# connectors.net
KiCad netlist of a schematic drawn in Altium Designer
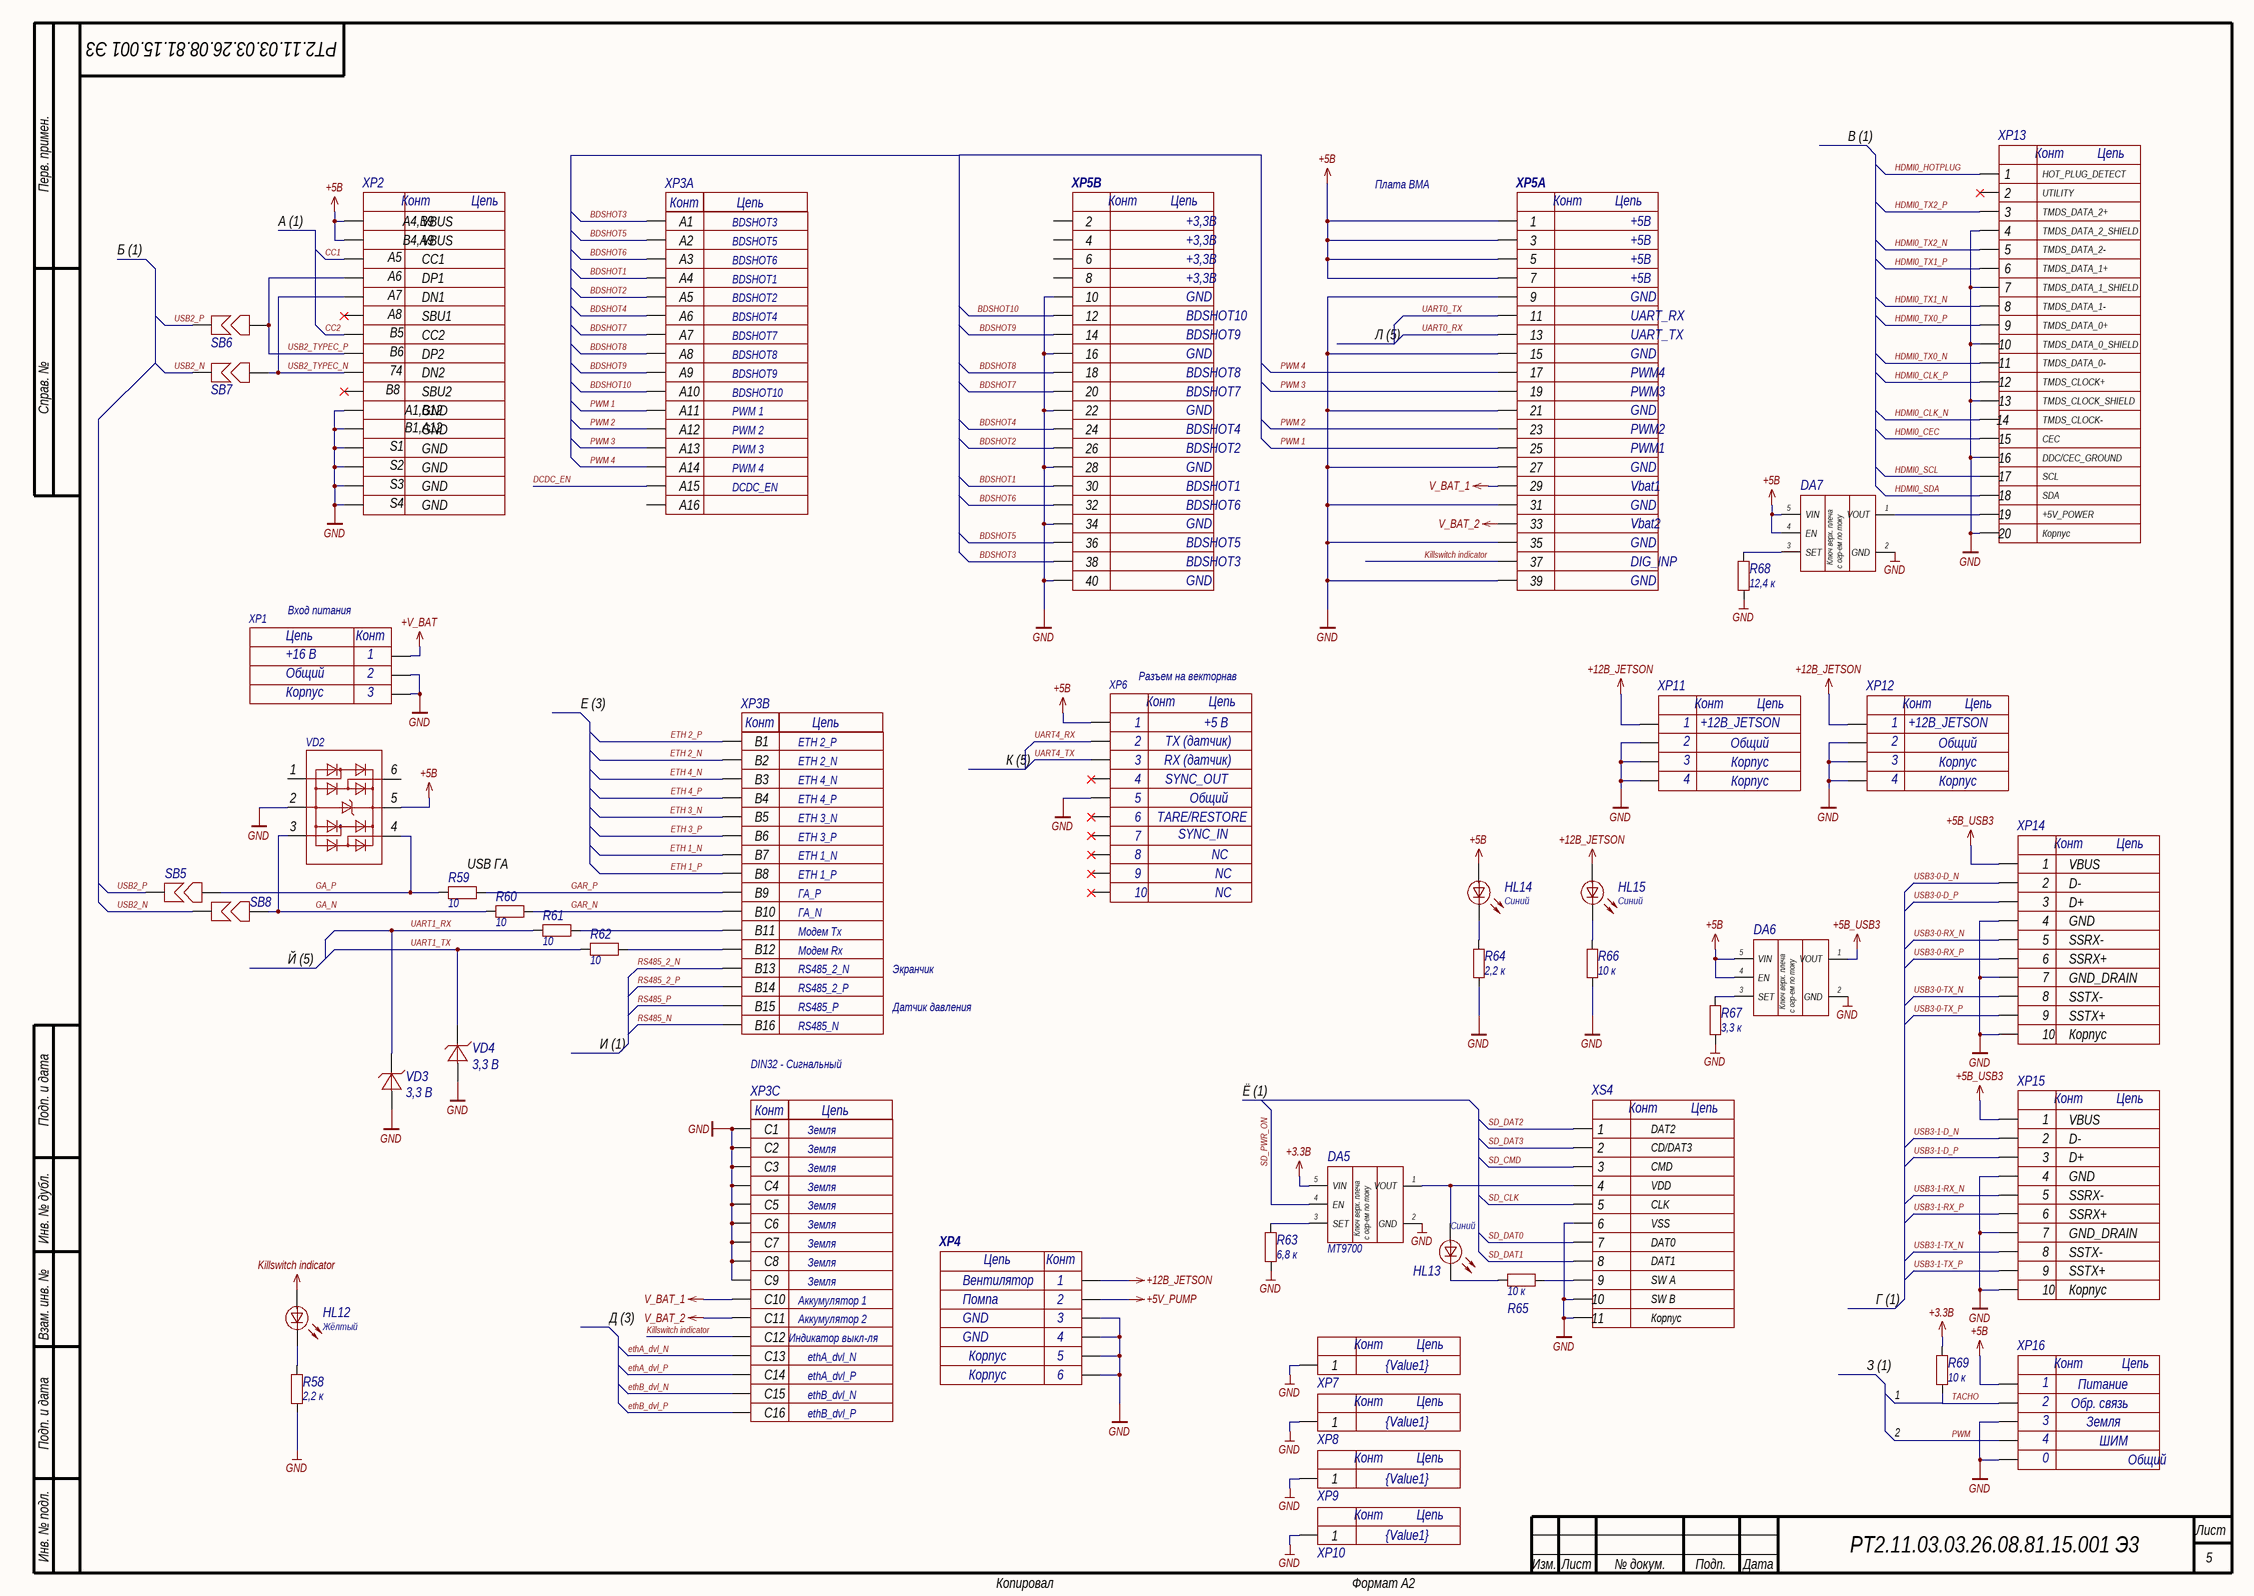
[diagram p0: connectors.SchDoc]

(export (version "E")
  (design (tool "Eeschema 10.0.6"))
  (components
    (comp (ref "DA5")
      (value "MT9700")
      (footprint "SOT23-5")
      (description "Силовой ключ с настраиваемым ограничением тока, 2А(max), SOT-23-5")
      (fields (field (name "АВТОР") "rreali"))
      (libsource (lib "Hydrolib") (part "MT9700"))
    )
    (comp (ref "DA6")
      (value "MT9700")
      (footprint "SOT23-5")
      (description "Силовой ключ с настраиваемым ограничением тока, 2А(max), SOT-23-5")
      (fields (field (name "АВТОР") "rreali"))
      (libsource (lib "Hydrolib") (part "MT9700"))
    )
    (comp (ref "DA7")
      (value "MT9700")
      (footprint "SOT23-5")
      (description "Силовой ключ с настраиваемым ограничением тока, 2А(max), SOT-23-5")
      (fields (field (name "АВТОР") "rreali"))
      (libsource (lib "Hydrolib") (part "MT9700"))
    )
    (comp (ref "HL12")
      (value "Жёлтый")
      (footprint "0603D_yellow")
      (description "Светодиод 0603 Жёлтый")
      (fields (field (name "PART NUMBER") "LED 0603 YELLOW") (field (name "АВТОР") "rreali"))
      (libsource (lib "Hydrolib") (part "LED"))
    )
    (comp (ref "HL13")
      (value "Синий")
      (footprint "0603D_blue")
      (description "Светодиод 0603 Синий")
      (fields (field (name "PART NUMBER") "LED 0603 BLUE") (field (name "АВТОР") "rreali"))
      (libsource (lib "Hydrolib") (part "LED"))
    )
    (comp (ref "HL14")
      (value "Синий")
      (footprint "0603D_blue")
      (description "Светодиод 0603 Синий")
      (fields (field (name "PART NUMBER") "LED 0603 BLUE") (field (name "АВТОР") "rreali"))
      (libsource (lib "Hydrolib") (part "LED"))
    )
    (comp (ref "HL15")
      (value "Синий")
      (footprint "0603D_blue")
      (description "Светодиод 0603 Синий")
      (fields (field (name "PART NUMBER") "LED 0603 BLUE") (field (name "АВТОР") "rreali"))
      (libsource (lib "Hydrolib") (part "LED"))
    )
    (comp (ref "R58")
      (value "2,2 к")
      (footprint "0603R")
      (description "Резистор номиналом 2,2 кОм 1%")
      (fields (field (name "PART NUMBER") "Resistor_2.2k_1_0603") (field (name "TOLERANCE") "1%"))
      (libsource (lib "") (part "Resistor_1"))
    )
    (comp (ref "R59")
      (value "10")
      (footprint "0603R")
      (description "Резистор номиналом 10 Ом 1%")
      (fields (field (name "PART NUMBER") "Resistor_10_1_0603") (field (name "TOLERANCE") "1%"))
      (libsource (lib "Hydrolib") (part "Resistor"))
    )
    (comp (ref "R60")
      (value "10")
      (footprint "0603R")
      (description "Резистор номиналом 10 Ом 1%")
      (fields (field (name "PART NUMBER") "Resistor_10_1_0603") (field (name "TOLERANCE") "1%"))
      (libsource (lib "Hydrolib") (part "Resistor"))
    )
    (comp (ref "R61")
      (value "10")
      (footprint "0603R")
      (description "Резистор номиналом 10 Ом 1%")
      (fields (field (name "PART NUMBER") "Resistor_10_1_0603") (field (name "TOLERANCE") "1%"))
      (libsource (lib "Hydrolib") (part "Resistor"))
    )
    (comp (ref "R62")
      (value "10")
      (footprint "0603R")
      (description "Резистор номиналом 10 Ом 1%")
      (fields (field (name "PART NUMBER") "Resistor_10_1_0603") (field (name "TOLERANCE") "1%"))
      (libsource (lib "Hydrolib") (part "Resistor"))
    )
    (comp (ref "R63")
      (value "6,8 к")
      (footprint "0603R")
      (description "Резистор номиналом 6,8 кОм 1%")
      (fields (field (name "PART NUMBER") "Resistor_6.8k_1_0603") (field (name "TOLERANCE") "1%"))
      (libsource (lib "") (part "Resistor_1"))
    )
    (comp (ref "R64")
      (value "2,2 к")
      (footprint "0603R")
      (description "Резистор номиналом 2,2 кОм 1%")
      (fields (field (name "PART NUMBER") "Resistor_2.2k_1_0603") (field (name "TOLERANCE") "1%"))
      (libsource (lib "") (part "Resistor_1"))
    )
    (comp (ref "R65")
      (value "10 к")
      (footprint "0603R")
      (description "Резистор номиналом 10 кОм 1%")
      (fields (field (name "PART NUMBER") "Resistor_10k_1_0603") (field (name "TOLERANCE") "1%"))
      (libsource (lib "Hydrolib") (part "Resistor"))
    )
    (comp (ref "R66")
      (value "10 к")
      (footprint "0603R")
      (description "Резистор номиналом 10 кОм 1%")
      (fields (field (name "PART NUMBER") "Resistor_10k_1_0603") (field (name "TOLERANCE") "1%"))
      (libsource (lib "") (part "Resistor_1"))
    )
    (comp (ref "R67")
      (value "3,3 к")
      (footprint "0603R")
      (description "Резистор номиналом 3,3 кОм 1%")
      (fields (field (name "PART NUMBER") "Resistor_3.3k_1_0603") (field (name "TOLERANCE") "1%"))
      (libsource (lib "") (part "Resistor_1"))
    )
    (comp (ref "R68")
      (value "12,4 к")
      (footprint "0603R")
      (description "Резистор номиналом 12,4 кОм 1%")
      (fields (field (name "PART NUMBER") "Resistor_12.4k_1_0603") (field (name "TOLERANCE") "1%"))
      (libsource (lib "") (part "Resistor_1"))
    )
    (comp (ref "R69")
      (value "10 к")
      (footprint "0603R")
      (description "Резистор номиналом 10 кОм 1%")
      (fields (field (name "PART NUMBER") "Resistor_10k_1_0603") (field (name "TOLERANCE") "1%"))
      (libsource (lib "") (part "Resistor_1"))
    )
    (comp (ref "SB5")
      (value "SB")
      (footprint "0603SB")
      (description "Solder bridge, мост припоя, запаиваемая перемычка, net tie, jumper")
      (fields (field (name "АВТОР") "rreali"))
      (libsource (lib "Hydrolib") (part "SB"))
    )
    (comp (ref "SB6")
      (value "SB")
      (footprint "0603SB")
      (description "Solder bridge, мост припоя, запаиваемая перемычка, net tie, jumper")
      (fields (field (name "АВТОР") "rreali"))
      (libsource (lib "Hydrolib") (part "SB"))
    )
    (comp (ref "SB7")
      (value "SB")
      (footprint "0603SB")
      (description "Solder bridge, мост припоя, запаиваемая перемычка, net tie, jumper")
      (fields (field (name "АВТОР") "rreali"))
      (libsource (lib "Hydrolib") (part "SB"))
    )
    (comp (ref "SB8")
      (value "SB")
      (footprint "0603SB")
      (description "Solder bridge, мост припоя, запаиваемая перемычка, net tie, jumper")
      (fields (field (name "АВТОР") "rreali"))
      (libsource (lib "Hydrolib") (part "SB"))
    )
    (comp (ref "VD2")
      (value "USBLC6-4")
      (footprint "SOT23-6")
      (description "Сборка защитных диодов для USB")
      (libsource (lib "Hydrolib") (part "USBLC6-4"))
    )
    (comp (ref "VD3")
      (value "3,3 В")
      (footprint "SOD523")
      (description "Защитный диод на 3,3 В, рассеиваемая мощность 45 Вт")
      (fields (field (name "PART NUMBER") "PESD3V3L1UB") (field (name "АВТОР") "glebmih"))
      (libsource (lib "Hydrolib") (part "TVS_1_1dir"))
    )
    (comp (ref "VD4")
      (value "3,3 В")
      (footprint "SOD523")
      (description "Защитный диод на 3,3 В, рассеиваемая мощность 45 Вт")
      (fields (field (name "PART NUMBER") "PESD3V3L1UB") (field (name "АВТОР") "glebmih"))
      (libsource (lib "Hydrolib") (part "TVS_1_1dir"))
    )
    (comp (ref "XP1")
      (value "XT30PW-M")
      (footprint "XT30PW-M")
      (description "30 А (15 продолжительно), 2 контакта разъем угловой отец")
      (fields
        (field (name "VALUE3") "Корпус")
        (field (name "VALUE2") "Общий")
        (field (name "VALUE1") "+16 В")
        (field (name "АВТОР") "rreali")
      )
      (libsource (lib "Hydrolib") (part "Polar_Conn_Shield"))
    )
    (comp (ref "XP2")
      (value "USB_type_C_16PF-026")
      (footprint "16PF-026")
      (description "USB2.0 TYPE-C 16PF-026, Разъём USB TYPE-C - розетка в плату")
      (fields (field (name "АВТОР") "rreali"))
      (libsource (lib "Hydrolib") (part "USB_type_C_16PF-026"))
    )
    (comp (ref "XP3")
      (value "DIN41612_48_3row_right_angle_male")
      (footprint "DIN41612_48_3row_right_angle_male")
      (fields (field (name "АВТОР") "glebmih"))
      (libsource (lib "Hydrolib") (part "Conn_48pin_3row"))
    )
    (comp (ref "XP4")
      (value "430450418")
      (footprint "MOLEX_430450418")
      (description "Разъем типа провод-плата, 3 мм, 4 контакт(-ов), Штыревой Разъем, для поверностного монтажа")
      (fields
        (field (name "VALUE1") "Вентилятор")
        (field (name "VALUE2") "Помпа")
        (field (name "VALUE3") "GND")
        (field (name "VALUE4") "GND")
        (field (name "PART NUMBER") "Molex_430450418")
        (field (name "АВТОР") "rreali")
      )
      (libsource (lib "Hydrolib") (part "Molex_430450415"))
    )
    (comp (ref "XP5")
      (value "DF40C-40DS")
      (footprint "DF40C-40DS")
      (description "Thruster control PCB")
      (libsource (lib "VMA") (part "DF40C-40DS"))
    )
    (comp (ref "XP6")
      (value "M80-4001042")
      (footprint "M80-4001042_govnodelie")
      (fields
        (field (name "VALUE1") "+5 В")
        (field (name "VALUE2") "TX (датчик)")
        (field (name "VALUE3") "RX (датчик)")
        (field (name "VALUE4") "SYNC_OUT")
        (field (name "VALUE5") "Общий")
        (field (name "VALUE6") "TARE/RESTORE")
        (field (name "VALUE7") "SYNC_IN")
        (field (name "VALUE8") "NC")
        (field (name "VALUE9") "NC")
        (field (name "VALUE10") "NC")
        (field (name "PART NUMBER") "Fucking M80-4001042")
        (field (name "АВТОР") "rreali")
      )
      (libsource (lib "Hydrolib") (part "Conn_10pin"))
    )
    (comp (ref "XP7")
      (value "SMT-NUT-M2H1.5")
      (footprint "9774015151")
      (fields (field (name "VALUE1") "{Value1}") (field (name "АВТОР") "glebmih"))
      (libsource (lib "Hydrolib") (part "Conn_1pin"))
    )
    (comp (ref "XP8")
      (value "SMT-NUT-M2H1.5")
      (footprint "9774015151")
      (fields (field (name "VALUE1") "{Value1}") (field (name "АВТОР") "glebmih"))
      (libsource (lib "Hydrolib") (part "Conn_1pin"))
    )
    (comp (ref "XP9")
      (value "SMT-NUT-M2H1.5")
      (footprint "9774015151")
      (fields (field (name "VALUE1") "{Value1}") (field (name "АВТОР") "glebmih"))
      (libsource (lib "Hydrolib") (part "Conn_1pin"))
    )
    (comp (ref "XP10")
      (value "SMT-NUT-M2H1.5")
      (footprint "9774015151")
      (fields (field (name "VALUE1") "{Value1}") (field (name "АВТОР") "glebmih"))
      (libsource (lib "Hydrolib") (part "Conn_1pin"))
    )
    (comp (ref "XP11")
      (value "430450218")
      (footprint "Molex_430450218")
      (fields
        (field (name "VALUE3") "Корпус")
        (field (name "VALUE2") "Общий")
        (field (name "VALUE4") "Корпус")
        (field (name "VALUE1") "+12В_JETSON")
        (field (name "PART NUMBER") "Molex_430450218")
        (field (name "АВТОР") "rreali")
      )
      (libsource (lib "Hydrolib") (part "Molex_430450218"))
    )
    (comp (ref "XP12")
      (value "430450218")
      (footprint "Molex_430450218")
      (fields
        (field (name "VALUE3") "Корпус")
        (field (name "VALUE2") "Общий")
        (field (name "VALUE4") "Корпус")
        (field (name "VALUE1") "+12В_JETSON")
        (field (name "PART NUMBER") "Molex_430450218")
        (field (name "АВТОР") "rreali")
      )
      (libsource (lib "Hydrolib") (part "Molex_430450218"))
    )
    (comp (ref "XP13")
      (value "467650001")
      (footprint "467650001")
      (fields (field (name "PART NUMBER") "467650001_microHDMI") (field (name "АВТОР") "rreali"))
      (libsource (lib "Hydrolib") (part "467650001"))
    )
    (comp (ref "XP14")
      (value "USB 3.0A DS1095-05")
      (footprint "USB3.0A_DS1095-05")
      (description "Разъем USB 3.0 тип A, 9 контактов, мама, угловой.")
      (fields (field (name "АВТОР") "rreali"))
      (libsource (lib "Hydrolib") (part "USB3.0A_DS1095-05"))
    )
    (comp (ref "XP15")
      (value "USB 3.0A DS1095-05")
      (footprint "USB3.0A_DS1095-05")
      (description "Разъем USB 3.0 тип A, 9 контактов, мама, угловой.")
      (fields (field (name "АВТОР") "rreali"))
      (libsource (lib "Hydrolib") (part "USB3.0A_DS1095-05"))
    )
    (comp (ref "XP16")
      (value "BM04B-SRSS-TB")
      (footprint "BM04B-SRSS-TB")
      (description "Разъем штыревой на плату, поверхностый монтаж, вертикальный, 4 контакта, шаг 1 мм")
      (fields
        (field (name "VALUE3") "Земля")
        (field (name "VALUE2") "Обр. связь")
        (field (name "VALUE4") "ШИМ")
        (field (name "VALUE1") "Питание")
        (field (name "АВТОР") "rreali")
      )
      (libsource (lib "Hydrolib") (part "Conn_4pin_sh"))
    )
    (comp (ref "XS4")
      (value "DM3AT-SF-PEJM5")
      (footprint "DM3AT-SF-PEJM5")
      (description "Разъем для microSD карты памяти угл.8к.1.1мм SMT")
      (fields (field (name "АВТОР") "rreali"))
      (libsource (lib "Hydrolib") (part "DM3AT-SF-PEJM5"))
    )
  )
  (nets
    (net (code "1") (name "+3.3В") (class "Default")
      (node (ref "DA5") (pin "5") (pinfunction "VIN_5") (pintype "passive"))
      (node (ref "R69") (pin "2") (pinfunction "2_2") (pintype "passive"))
    )
    (net (code "2") (name "+5V_PUMP") (class "Default")
      (node (ref "XP4") (pin "2") (pinfunction "2_2") (pintype "passive"))
    )
    (net (code "3") (name "+5В") (class "Default")
      (node (ref "DA6") (pin "4") (pinfunction "EN_4") (pintype "passive"))
      (node (ref "DA6") (pin "5") (pinfunction "VIN_5") (pintype "passive"))
      (node (ref "DA7") (pin "4") (pinfunction "EN_4") (pintype "passive"))
      (node (ref "DA7") (pin "5") (pinfunction "VIN_5") (pintype "passive"))
      (node (ref "HL14") (pin "1") (pinfunction "1_1") (pintype "passive"))
      (node (ref "VD2") (pin "5") (pinfunction "13_5") (pintype "passive"))
      (node (ref "XP16") (pin "1") (pinfunction "1_1") (pintype "passive"))
      (node (ref "XP2") (pin "A4/B9") (pinfunction "VBUS_A4/B9") (pintype "passive"))
      (node (ref "XP2") (pin "B4/A9") (pinfunction "VBUS_B4/A9") (pintype "passive"))
      (node (ref "XP5") (pin "1") (pinfunction "1_1") (pintype "passive"))
      (node (ref "XP5") (pin "3") (pinfunction "3_3") (pintype "passive"))
      (node (ref "XP5") (pin "5") (pinfunction "5_5") (pintype "passive"))
      (node (ref "XP5") (pin "7") (pinfunction "7_7") (pintype "passive"))
      (node (ref "XP6") (pin "1") (pinfunction "1_1") (pintype "passive"))
    )
    (net (code "4") (name "+5В_USB3") (class "Default")
      (node (ref "DA6") (pin "1") (pinfunction "VOUT_1") (pintype "passive"))
      (node (ref "XP14") (pin "1") (pinfunction "VBUS_1") (pintype "passive"))
      (node (ref "XP15") (pin "1") (pinfunction "VBUS_1") (pintype "passive"))
    )
    (net (code "5") (name "+12В_JETSON") (class "Default")
      (node (ref "HL15") (pin "1") (pinfunction "1_1") (pintype "passive"))
      (node (ref "XP11") (pin "1") (pinfunction "1_1") (pintype "passive"))
      (node (ref "XP12") (pin "1") (pinfunction "1_1") (pintype "passive"))
      (node (ref "XP4") (pin "1") (pinfunction "1_1") (pintype "passive"))
    )
    (net (code "6") (name "+V_BAT") (class "Default")
      (node (ref "XP1") (pin "P") (pinfunction "P_P") (pintype "passive"))
    )
    (net (code "7") (name "/BDSHOT1") (class "Default")
      (node (ref "XP3") (pin "A4") (pinfunction "A4_A4") (pintype "passive"))
      (node (ref "XP5") (pin "30") (pinfunction "30_30") (pintype "passive"))
    )
    (net (code "8") (name "/BDSHOT2") (class "Default")
      (node (ref "XP3") (pin "A5") (pinfunction "A5_A5") (pintype "passive"))
      (node (ref "XP5") (pin "26") (pinfunction "26_26") (pintype "passive"))
    )
    (net (code "9") (name "/BDSHOT3") (class "Default")
      (node (ref "XP3") (pin "A1") (pinfunction "A1_A1") (pintype "passive"))
      (node (ref "XP5") (pin "38") (pinfunction "38_38") (pintype "passive"))
    )
    (net (code "10") (name "/BDSHOT4") (class "Default")
      (node (ref "XP3") (pin "A6") (pinfunction "A6_A6") (pintype "passive"))
      (node (ref "XP5") (pin "24") (pinfunction "24_24") (pintype "passive"))
    )
    (net (code "11") (name "/BDSHOT5") (class "Default")
      (node (ref "XP3") (pin "A2") (pinfunction "A2_A2") (pintype "passive"))
      (node (ref "XP5") (pin "36") (pinfunction "36_36") (pintype "passive"))
    )
    (net (code "12") (name "/BDSHOT6") (class "Default")
      (node (ref "XP3") (pin "A3") (pinfunction "A3_A3") (pintype "passive"))
      (node (ref "XP5") (pin "32") (pinfunction "32_32") (pintype "passive"))
    )
    (net (code "13") (name "/BDSHOT7") (class "Default")
      (node (ref "XP3") (pin "A7") (pinfunction "A7_A7") (pintype "passive"))
      (node (ref "XP5") (pin "20") (pinfunction "20_20") (pintype "passive"))
    )
    (net (code "14") (name "/BDSHOT8") (class "Default")
      (node (ref "XP3") (pin "A8") (pinfunction "A8_A8") (pintype "passive"))
      (node (ref "XP5") (pin "18") (pinfunction "18_18") (pintype "passive"))
    )
    (net (code "15") (name "/BDSHOT9") (class "Default")
      (node (ref "XP3") (pin "A9") (pinfunction "A9_A9") (pintype "passive"))
      (node (ref "XP5") (pin "14") (pinfunction "14_14") (pintype "passive"))
    )
    (net (code "16") (name "/BDSHOT10") (class "Default")
      (node (ref "XP3") (pin "A10") (pinfunction "A10_A10") (pintype "passive"))
      (node (ref "XP5") (pin "12") (pinfunction "12_12") (pintype "passive"))
    )
    (net (code "17") (name "/CC1") (class "Default")
      (node (ref "XP2") (pin "A5") (pinfunction "CC1_A5") (pintype "passive"))
    )
    (net (code "18") (name "/CC2") (class "Default")
      (node (ref "XP2") (pin "B5") (pinfunction "CC2_B5") (pintype "passive"))
    )
    (net (code "19") (name "/DCDC_EN") (class "Default")
      (node (ref "XP3") (pin "A15") (pinfunction "A15_A15") (pintype "passive"))
    )
    (net (code "20") (name "/ETH 1_N") (class "Default")
      (node (ref "XP3") (pin "B7") (pinfunction "B7_B7") (pintype "passive"))
    )
    (net (code "21") (name "/ETH 1_P") (class "Default")
      (node (ref "XP3") (pin "B8") (pinfunction "B8_B8") (pintype "passive"))
    )
    (net (code "22") (name "/ETH 2_N") (class "Default")
      (node (ref "XP3") (pin "B2") (pinfunction "B2_B2") (pintype "passive"))
    )
    (net (code "23") (name "/ETH 2_P") (class "Default")
      (node (ref "XP3") (pin "B1") (pinfunction "B1_B1") (pintype "passive"))
    )
    (net (code "24") (name "/ETH 3_N") (class "Default")
      (node (ref "XP3") (pin "B5") (pinfunction "B5_B5") (pintype "passive"))
    )
    (net (code "25") (name "/ETH 3_P") (class "Default")
      (node (ref "XP3") (pin "B6") (pinfunction "B6_B6") (pintype "passive"))
    )
    (net (code "26") (name "/ETH 4_N") (class "Default")
      (node (ref "XP3") (pin "B3") (pinfunction "B3_B3") (pintype "passive"))
    )
    (net (code "27") (name "/ETH 4_P") (class "Default")
      (node (ref "XP3") (pin "B4") (pinfunction "B4_B4") (pintype "passive"))
    )
    (net (code "28") (name "/GAR_N") (class "Default")
      (node (ref "R60") (pin "2") (pinfunction "2_2") (pintype "passive"))
      (node (ref "XP3") (pin "B10") (pinfunction "B10_B10") (pintype "passive"))
    )
    (net (code "29") (name "/GAR_P") (class "Default")
      (node (ref "R59") (pin "2") (pinfunction "2_2") (pintype "passive"))
      (node (ref "XP3") (pin "B9") (pinfunction "B9_B9") (pintype "passive"))
    )
    (net (code "30") (name "/GA_N") (class "Default")
      (node (ref "R60") (pin "1") (pinfunction "1_1") (pintype "passive"))
      (node (ref "SB8") (pin "1") (pinfunction "1_1") (pintype "passive"))
      (node (ref "VD2") (pin "3") (pinfunction "11_3") (pintype "passive"))
    )
    (net (code "31") (name "/GA_P") (class "Default")
      (node (ref "R59") (pin "1") (pinfunction "1_1") (pintype "passive"))
      (node (ref "SB5") (pin "1") (pinfunction "1_1") (pintype "passive"))
      (node (ref "VD2") (pin "4") (pinfunction "12_4") (pintype "passive"))
    )
    (net (code "32") (name "/HDMI0_CEC") (class "Default")
      (node (ref "XP13") (pin "15") (pinfunction "CEC_15") (pintype "passive"))
    )
    (net (code "33") (name "/HDMI0_CLK_N") (class "Default")
      (node (ref "XP13") (pin "14") (pinfunction "TMDS_CLOCK-_14") (pintype "passive"))
    )
    (net (code "34") (name "/HDMI0_CLK_P") (class "Default")
      (node (ref "XP13") (pin "12") (pinfunction "TMDS_CLOCK+_12") (pintype "passive"))
    )
    (net (code "35") (name "/HDMI0_HOTPLUG") (class "Default")
      (node (ref "XP13") (pin "1") (pinfunction "HOT_PLUG_DETECT_1") (pintype "passive"))
    )
    (net (code "36") (name "/HDMI0_SCL") (class "Default")
      (node (ref "XP13") (pin "17") (pinfunction "SCL_17") (pintype "passive"))
    )
    (net (code "37") (name "/HDMI0_SDA") (class "Default")
      (node (ref "XP13") (pin "18") (pinfunction "SDA_18") (pintype "passive"))
    )
    (net (code "38") (name "/HDMI0_TX0_N") (class "Default")
      (node (ref "XP13") (pin "11") (pinfunction "TMDS_DATA_0-_11") (pintype "passive"))
    )
    (net (code "39") (name "/HDMI0_TX0_P") (class "Default")
      (node (ref "XP13") (pin "9") (pinfunction "TMDS_DATA_0+_9") (pintype "passive"))
    )
    (net (code "40") (name "/HDMI0_TX1_N") (class "Default")
      (node (ref "XP13") (pin "8") (pinfunction "TMDS_DATA_1-_8") (pintype "passive"))
    )
    (net (code "41") (name "/HDMI0_TX1_P") (class "Default")
      (node (ref "XP13") (pin "6") (pinfunction "TMDS_DATA_1+_6") (pintype "passive"))
    )
    (net (code "42") (name "/HDMI0_TX2_N") (class "Default")
      (node (ref "XP13") (pin "5") (pinfunction "TMDS_DATA_2-_5") (pintype "passive"))
    )
    (net (code "43") (name "/HDMI0_TX2_P") (class "Default")
      (node (ref "XP13") (pin "3") (pinfunction "TMDS_DATA_2+_3") (pintype "passive"))
    )
    (net (code "44") (name "/PWM") (class "Default")
      (node (ref "XP16") (pin "4") (pinfunction "4_4") (pintype "passive"))
    )
    (net (code "45") (name "/PWM 1") (class "Default")
      (node (ref "XP3") (pin "A11") (pinfunction "A11_A11") (pintype "passive"))
      (node (ref "XP5") (pin "25") (pinfunction "25_25") (pintype "passive"))
    )
    (net (code "46") (name "/PWM 2") (class "Default")
      (node (ref "XP3") (pin "A12") (pinfunction "A12_A12") (pintype "passive"))
      (node (ref "XP5") (pin "23") (pinfunction "23_23") (pintype "passive"))
    )
    (net (code "47") (name "/PWM 3") (class "Default")
      (node (ref "XP3") (pin "A13") (pinfunction "A13_A13") (pintype "passive"))
      (node (ref "XP5") (pin "19") (pinfunction "19_19") (pintype "passive"))
    )
    (net (code "48") (name "/PWM 4") (class "Default")
      (node (ref "XP3") (pin "A14") (pinfunction "A14_A14") (pintype "passive"))
      (node (ref "XP5") (pin "17") (pinfunction "17_17") (pintype "passive"))
    )
    (net (code "49") (name "/RS485_2_N") (class "Default")
      (node (ref "XP3") (pin "B13") (pinfunction "B13_B13") (pintype "passive"))
    )
    (net (code "50") (name "/RS485_2_P") (class "Default")
      (node (ref "XP3") (pin "B14") (pinfunction "B14_B14") (pintype "passive"))
    )
    (net (code "51") (name "/RS485_N") (class "Default")
      (node (ref "XP3") (pin "B16") (pinfunction "B16_B16") (pintype "passive"))
    )
    (net (code "52") (name "/RS485_P") (class "Default")
      (node (ref "XP3") (pin "B15") (pinfunction "B15_B15") (pintype "passive"))
    )
    (net (code "53") (name "/SD_CLK") (class "Default")
      (node (ref "XS4") (pin "5") (pinfunction "CLK_5") (pintype "passive"))
    )
    (net (code "54") (name "/SD_CMD") (class "Default")
      (node (ref "XS4") (pin "3") (pinfunction "CMD_3") (pintype "passive"))
    )
    (net (code "55") (name "/SD_DAT0") (class "Default")
      (node (ref "XS4") (pin "7") (pinfunction "DAT0_7") (pintype "passive"))
    )
    (net (code "56") (name "/SD_DAT1") (class "Default")
      (node (ref "XS4") (pin "8") (pinfunction "DAT1_8") (pintype "passive"))
    )
    (net (code "57") (name "/SD_DAT2") (class "Default")
      (node (ref "XS4") (pin "1") (pinfunction "DAT2_1") (pintype "passive"))
    )
    (net (code "58") (name "/SD_DAT3") (class "Default")
      (node (ref "XS4") (pin "2") (pinfunction "CD/DAT3_2") (pintype "passive"))
    )
    (net (code "59") (name "/SD_PWR_ON") (class "Default")
      (node (ref "DA5") (pin "4") (pinfunction "EN_4") (pintype "passive"))
    )
    (net (code "60") (name "/TACHO") (class "Default")
      (node (ref "R69") (pin "1") (pinfunction "1_1") (pintype "passive"))
      (node (ref "XP16") (pin "2") (pinfunction "2_2") (pintype "passive"))
    )
    (net (code "61") (name "/UART0_RX") (class "Default")
      (node (ref "XP5") (pin "13") (pinfunction "13_13") (pintype "passive"))
    )
    (net (code "62") (name "/UART0_TX") (class "Default")
      (node (ref "XP5") (pin "11") (pinfunction "11_11") (pintype "passive"))
    )
    (net (code "63") (name "/UART1_RX") (class "Default")
      (node (ref "R61") (pin "1") (pinfunction "1_1") (pintype "passive"))
      (node (ref "VD3") (pin "2") (pinfunction "2_2") (pintype "passive"))
    )
    (net (code "64") (name "/UART1_TX") (class "Default")
      (node (ref "R62") (pin "1") (pinfunction "1_1") (pintype "passive"))
      (node (ref "VD4") (pin "2") (pinfunction "2_2") (pintype "passive"))
    )
    (net (code "65") (name "/UART4_RX") (class "Default")
      (node (ref "XP6") (pin "2") (pinfunction "2_2") (pintype "passive"))
    )
    (net (code "66") (name "/UART4_TX") (class "Default")
      (node (ref "XP6") (pin "3") (pinfunction "3_3") (pintype "passive"))
    )
    (net (code "67") (name "/USB2_N") (class "Default")
      (node (ref "SB7") (pin "2") (pinfunction "2_2") (pintype "passive"))
      (node (ref "SB8") (pin "2") (pinfunction "2_2") (pintype "passive"))
    )
    (net (code "68") (name "/USB2_P") (class "Default")
      (node (ref "SB5") (pin "2") (pinfunction "2_2") (pintype "passive"))
      (node (ref "SB6") (pin "2") (pinfunction "2_2") (pintype "passive"))
    )
    (net (code "69") (name "/USB2_TYPEC_N") (class "Default")
      (node (ref "SB7") (pin "1") (pinfunction "1_1") (pintype "passive"))
      (node (ref "XP2") (pin "A7") (pinfunction "DN1_A7") (pintype "passive"))
      (node (ref "XP2") (pin "B7") (pinfunction "DN2_B7") (pintype "passive"))
    )
    (net (code "70") (name "/USB2_TYPEC_P") (class "Default")
      (node (ref "SB6") (pin "1") (pinfunction "1_1") (pintype "passive"))
      (node (ref "XP2") (pin "A6") (pinfunction "DP1_A6") (pintype "passive"))
      (node (ref "XP2") (pin "B6") (pinfunction "DP2_B6") (pintype "passive"))
    )
    (net (code "71") (name "/USB3-0-D_N") (class "Default")
      (node (ref "XP14") (pin "2") (pinfunction "D-_2") (pintype "passive"))
    )
    (net (code "72") (name "/USB3-0-D_P") (class "Default")
      (node (ref "XP14") (pin "3") (pinfunction "D+_3") (pintype "passive"))
    )
    (net (code "73") (name "/USB3-0-RX_N") (class "Default")
      (node (ref "XP14") (pin "5") (pinfunction "SSRX-_5") (pintype "passive"))
    )
    (net (code "74") (name "/USB3-0-RX_P") (class "Default")
      (node (ref "XP14") (pin "6") (pinfunction "SSRX+_6") (pintype "passive"))
    )
    (net (code "75") (name "/USB3-0-TX_N") (class "Default")
      (node (ref "XP14") (pin "8") (pinfunction "SSTX-_8") (pintype "passive"))
    )
    (net (code "76") (name "/USB3-0-TX_P") (class "Default")
      (node (ref "XP14") (pin "9") (pinfunction "SSTX+_9") (pintype "passive"))
    )
    (net (code "77") (name "/USB3-1-D_N") (class "Default")
      (node (ref "XP15") (pin "2") (pinfunction "D-_2") (pintype "passive"))
    )
    (net (code "78") (name "/USB3-1-D_P") (class "Default")
      (node (ref "XP15") (pin "3") (pinfunction "D+_3") (pintype "passive"))
    )
    (net (code "79") (name "/USB3-1-RX_N") (class "Default")
      (node (ref "XP15") (pin "5") (pinfunction "SSRX-_5") (pintype "passive"))
    )
    (net (code "80") (name "/USB3-1-RX_P") (class "Default")
      (node (ref "XP15") (pin "6") (pinfunction "SSRX+_6") (pintype "passive"))
    )
    (net (code "81") (name "/USB3-1-TX_N") (class "Default")
      (node (ref "XP15") (pin "8") (pinfunction "SSTX-_8") (pintype "passive"))
    )
    (net (code "82") (name "/USB3-1-TX_P") (class "Default")
      (node (ref "XP15") (pin "9") (pinfunction "SSTX+_9") (pintype "passive"))
    )
    (net (code "83") (name "/ethA_dvl_N") (class "Default")
      (node (ref "XP3") (pin "C13") (pinfunction "C13_C13") (pintype "passive"))
    )
    (net (code "84") (name "/ethA_dvl_P") (class "Default")
      (node (ref "XP3") (pin "C14") (pinfunction "C14_C14") (pintype "passive"))
    )
    (net (code "85") (name "/ethB_dvl_N") (class "Default")
      (node (ref "XP3") (pin "C15") (pinfunction "C15_C15") (pintype "passive"))
    )
    (net (code "86") (name "/ethB_dvl_P") (class "Default")
      (node (ref "XP3") (pin "C16") (pinfunction "C16_C16") (pintype "passive"))
    )
    (net (code "87") (name "GND") (class "Default")
      (node (ref "DA5") (pin "2") (pinfunction "GND_2") (pintype "passive"))
      (node (ref "DA6") (pin "2") (pinfunction "GND_2") (pintype "passive"))
      (node (ref "DA7") (pin "2") (pinfunction "GND_2") (pintype "passive"))
      (node (ref "R58") (pin "1") (pinfunction "1_1") (pintype "passive"))
      (node (ref "R63") (pin "1") (pinfunction "1_1") (pintype "passive"))
      (node (ref "R64") (pin "1") (pinfunction "1_1") (pintype "passive"))
      (node (ref "R66") (pin "1") (pinfunction "1_1") (pintype "passive"))
      (node (ref "R67") (pin "1") (pinfunction "1_1") (pintype "passive"))
      (node (ref "R68") (pin "1") (pinfunction "1_1") (pintype "passive"))
      (node (ref "VD2") (pin "2") (pinfunction "10_2") (pintype "passive"))
      (node (ref "VD3") (pin "1") (pinfunction "1_1") (pintype "passive"))
      (node (ref "VD4") (pin "1") (pinfunction "1_1") (pintype "passive"))
      (node (ref "XP1") (pin "0") (pinfunction "0_0") (pintype "passive"))
      (node (ref "XP1") (pin "N") (pinfunction "N_N") (pintype "passive"))
      (node (ref "XP10") (pin "1") (pinfunction "1_1") (pintype "passive"))
      (node (ref "XP11") (pin "0") (pinfunction "0_0") (pintype "passive"))
      (node (ref "XP11") (pin "2") (pinfunction "2_2") (pintype "passive"))
      (node (ref "XP12") (pin "0") (pinfunction "0_0") (pintype "passive"))
      (node (ref "XP12") (pin "2") (pinfunction "2_2") (pintype "passive"))
      (node (ref "XP13") (pin "10") (pinfunction "TMDS_DATA_0_SHIELD_10") (pintype "passive"))
      (node (ref "XP13") (pin "13") (pinfunction "TMDS_CLOCK_SHIELD_13") (pintype "passive"))
      (node (ref "XP13") (pin "16") (pinfunction "DDC/CEC_GROUND_16") (pintype "passive"))
      (node (ref "XP13") (pin "4") (pinfunction "TMDS_DATA_2_SHIELD_4") (pintype "passive"))
      (node (ref "XP13") (pin "7") (pinfunction "TMDS_DATA_1_SHIELD_7") (pintype "passive"))
      (node (ref "XP13") (pin "SH") (pinfunction "Корпус_SH") (pintype "passive"))
      (node (ref "XP14") (pin "0") (pinfunction "Корпус_0") (pintype "passive"))
      (node (ref "XP14") (pin "4") (pinfunction "GND_4") (pintype "passive"))
      (node (ref "XP14") (pin "7") (pinfunction "GND_DRAIN_7") (pintype "passive"))
      (node (ref "XP15") (pin "0") (pinfunction "Корпус_0") (pintype "passive"))
      (node (ref "XP15") (pin "4") (pinfunction "GND_4") (pintype "passive"))
      (node (ref "XP15") (pin "7") (pinfunction "GND_DRAIN_7") (pintype "passive"))
      (node (ref "XP16") (pin "0") (pinfunction "0_0") (pintype "passive"))
      (node (ref "XP16") (pin "3") (pinfunction "3_3") (pintype "passive"))
      (node (ref "XP2") (pin "A1/B12") (pinfunction "GND_A1/B12") (pintype "passive"))
      (node (ref "XP2") (pin "B1/A12") (pinfunction "GND_B1/A12") (pintype "passive"))
      (node (ref "XP2") (pin "S1") (pinfunction "GND_S1") (pintype "passive"))
      (node (ref "XP2") (pin "S2") (pinfunction "GND_S2") (pintype "passive"))
      (node (ref "XP2") (pin "S3") (pinfunction "GND_S3") (pintype "passive"))
      (node (ref "XP2") (pin "S4") (pinfunction "GND_S4") (pintype "passive"))
      (node (ref "XP3") (pin "C1") (pinfunction "C1_C1") (pintype "passive"))
      (node (ref "XP3") (pin "C2") (pinfunction "C2_C2") (pintype "passive"))
      (node (ref "XP3") (pin "C3") (pinfunction "C3_C3") (pintype "passive"))
      (node (ref "XP3") (pin "C4") (pinfunction "C4_C4") (pintype "passive"))
      (node (ref "XP3") (pin "C5") (pinfunction "C5_C5") (pintype "passive"))
      (node (ref "XP3") (pin "C6") (pinfunction "C6_C6") (pintype "passive"))
      (node (ref "XP3") (pin "C7") (pinfunction "C7_C7") (pintype "passive"))
      (node (ref "XP3") (pin "C8") (pinfunction "C8_C8") (pintype "passive"))
      (node (ref "XP3") (pin "C9") (pinfunction "C9_C9") (pintype "passive"))
      (node (ref "XP4") (pin "0") (pinfunction "0_0") (pintype "passive"))
      (node (ref "XP4") (pin "3") (pinfunction "3_3") (pintype "passive"))
      (node (ref "XP4") (pin "4") (pinfunction "4_4") (pintype "passive"))
      (node (ref "XP5") (pin "10") (pinfunction "10_10") (pintype "passive"))
      (node (ref "XP5") (pin "15") (pinfunction "15_15") (pintype "passive"))
      (node (ref "XP5") (pin "16") (pinfunction "16_16") (pintype "passive"))
      (node (ref "XP5") (pin "21") (pinfunction "21_21") (pintype "passive"))
      (node (ref "XP5") (pin "22") (pinfunction "22_22") (pintype "passive"))
      (node (ref "XP5") (pin "27") (pinfunction "27_27") (pintype "passive"))
      (node (ref "XP5") (pin "28") (pinfunction "28_28") (pintype "passive"))
      (node (ref "XP5") (pin "31") (pinfunction "31_31") (pintype "passive"))
      (node (ref "XP5") (pin "34") (pinfunction "34_34") (pintype "passive"))
      (node (ref "XP5") (pin "35") (pinfunction "35_35") (pintype "passive"))
      (node (ref "XP5") (pin "39") (pinfunction "39_39") (pintype "passive"))
      (node (ref "XP5") (pin "40") (pinfunction "40_40") (pintype "passive"))
      (node (ref "XP5") (pin "9") (pinfunction "9_9") (pintype "passive"))
      (node (ref "XP6") (pin "5") (pinfunction "5_5") (pintype "passive"))
      (node (ref "XP7") (pin "1") (pinfunction "1_1") (pintype "passive"))
      (node (ref "XP8") (pin "1") (pinfunction "1_1") (pintype "passive"))
      (node (ref "XP9") (pin "1") (pinfunction "1_1") (pintype "passive"))
      (node (ref "XS4") (pin "6") (pinfunction "VSS_6") (pintype "passive"))
      (node (ref "XS4") (pin "SH") (pinfunction "Корпус_SH") (pintype "passive"))
      (node (ref "XS4") (pin "SWB") (pinfunction "SW_B_SWB") (pintype "passive"))
    )
    (net (code "88") (name "Killswitch indicator") (class "Default")
      (node (ref "HL12") (pin "1") (pinfunction "1_1") (pintype "passive"))
      (node (ref "XP3") (pin "C12") (pinfunction "C12_C12") (pintype "passive"))
      (node (ref "XP5") (pin "37") (pinfunction "37_37") (pintype "passive"))
    )
    (net (code "89") (name "Net-(DA5-SET)") (class "Default")
      (node (ref "DA5") (pin "3") (pinfunction "SET_3") (pintype "passive"))
      (node (ref "R63") (pin "2") (pinfunction "2_2") (pintype "passive"))
    )
    (net (code "90") (name "Net-(DA5-VOUT)") (class "Default")
      (node (ref "DA5") (pin "1") (pinfunction "VOUT_1") (pintype "passive"))
      (node (ref "HL13") (pin "1") (pinfunction "1_1") (pintype "passive"))
      (node (ref "XS4") (pin "4") (pinfunction "VDD_4") (pintype "passive"))
    )
    (net (code "91") (name "Net-(DA6-SET)") (class "Default")
      (node (ref "DA6") (pin "3") (pinfunction "SET_3") (pintype "passive"))
      (node (ref "R67") (pin "2") (pinfunction "2_2") (pintype "passive"))
    )
    (net (code "92") (name "Net-(DA7-SET)") (class "Default")
      (node (ref "DA7") (pin "3") (pinfunction "SET_3") (pintype "passive"))
      (node (ref "R68") (pin "2") (pinfunction "2_2") (pintype "passive"))
    )
    (net (code "93") (name "Net-(DA7-VOUT)") (class "Default")
      (node (ref "DA7") (pin "1") (pinfunction "VOUT_1") (pintype "passive"))
      (node (ref "XP13") (pin "19") (pinfunction "+5V_POWER_19") (pintype "passive"))
    )
    (net (code "94") (name "Net-(HL12-Pad2)") (class "Default")
      (node (ref "HL12") (pin "2") (pinfunction "2_2") (pintype "passive"))
      (node (ref "R58") (pin "2") (pinfunction "2_2") (pintype "passive"))
    )
    (net (code "95") (name "Net-(HL13-Pad2)") (class "Default")
      (node (ref "HL13") (pin "2") (pinfunction "2_2") (pintype "passive"))
      (node (ref "R65") (pin "1") (pinfunction "1_1") (pintype "passive"))
    )
    (net (code "96") (name "Net-(HL14-Pad2)") (class "Default")
      (node (ref "HL14") (pin "2") (pinfunction "2_2") (pintype "passive"))
      (node (ref "R64") (pin "2") (pinfunction "2_2") (pintype "passive"))
    )
    (net (code "97") (name "Net-(HL15-Pad2)") (class "Default")
      (node (ref "HL15") (pin "2") (pinfunction "2_2") (pintype "passive"))
      (node (ref "R66") (pin "2") (pinfunction "2_2") (pintype "passive"))
    )
    (net (code "98") (name "Net-(R61-Pad2)") (class "Default")
      (node (ref "R61") (pin "2") (pinfunction "2_2") (pintype "passive"))
      (node (ref "XP3") (pin "B11") (pinfunction "B11_B11") (pintype "passive"))
    )
    (net (code "99") (name "Net-(R62-Pad2)") (class "Default")
      (node (ref "R62") (pin "2") (pinfunction "2_2") (pintype "passive"))
      (node (ref "XP3") (pin "B12") (pinfunction "B12_B12") (pintype "passive"))
    )
    (net (code "100") (name "Net-(XS4-SW_A)") (class "Default")
      (node (ref "R65") (pin "2") (pinfunction "2_2") (pintype "passive"))
      (node (ref "XS4") (pin "SWA") (pinfunction "SW_A_SWA") (pintype "passive"))
    )
    (net (code "101") (name "V_BAT_1") (class "Default")
      (node (ref "XP3") (pin "C10") (pinfunction "C10_C10") (pintype "passive"))
      (node (ref "XP5") (pin "29") (pinfunction "29_29") (pintype "passive"))
    )
    (net (code "102") (name "V_BAT_2") (class "Default")
      (node (ref "XP3") (pin "C11") (pinfunction "C11_C11") (pintype "passive"))
      (node (ref "XP5") (pin "33") (pinfunction "33_33") (pintype "passive"))
    )
    (net (code "103") (name "unconnected-(VD2-9-Pad1)") (class "Default")
      (node (ref "VD2") (pin "1") (pinfunction "9_1") (pintype "passive"))
    )
    (net (code "104") (name "unconnected-(VD2-14-Pad6)") (class "Default")
      (node (ref "VD2") (pin "6") (pinfunction "14_6") (pintype "passive"))
    )
    (net (code "105") (name "unconnected-(XP2-SBU1-PadA8)") (class "Default")
      (node (ref "XP2") (pin "A8") (pinfunction "SBU1_A8") (pintype "passive+no_connect"))
    )
    (net (code "106") (name "unconnected-(XP2-SBU2-PadB8)") (class "Default")
      (node (ref "XP2") (pin "B8") (pinfunction "SBU2_B8") (pintype "passive+no_connect"))
    )
    (net (code "107") (name "unconnected-(XP3-PadA16)") (class "Default")
      (node (ref "XP3") (pin "A16") (pinfunction "A16_A16") (pintype "passive"))
    )
    (net (code "108") (name "unconnected-(XP5-Pad2)") (class "Default")
      (node (ref "XP5") (pin "2") (pinfunction "2_2") (pintype "passive"))
    )
    (net (code "109") (name "unconnected-(XP5-Pad4)") (class "Default")
      (node (ref "XP5") (pin "4") (pinfunction "4_4") (pintype "passive"))
    )
    (net (code "110") (name "unconnected-(XP5-Pad6)") (class "Default")
      (node (ref "XP5") (pin "6") (pinfunction "6_6") (pintype "passive"))
    )
    (net (code "111") (name "unconnected-(XP5-Pad8)") (class "Default")
      (node (ref "XP5") (pin "8") (pinfunction "8_8") (pintype "passive"))
    )
    (net (code "112") (name "unconnected-(XP6-Pad4)") (class "Default")
      (node (ref "XP6") (pin "4") (pinfunction "4_4") (pintype "passive+no_connect"))
    )
    (net (code "113") (name "unconnected-(XP6-Pad6)") (class "Default")
      (node (ref "XP6") (pin "6") (pinfunction "6_6") (pintype "passive+no_connect"))
    )
    (net (code "114") (name "unconnected-(XP6-Pad7)") (class "Default")
      (node (ref "XP6") (pin "7") (pinfunction "7_7") (pintype "passive+no_connect"))
    )
    (net (code "115") (name "unconnected-(XP6-Pad8)") (class "Default")
      (node (ref "XP6") (pin "8") (pinfunction "8_8") (pintype "passive+no_connect"))
    )
    (net (code "116") (name "unconnected-(XP6-Pad9)") (class "Default")
      (node (ref "XP6") (pin "9") (pinfunction "9_9") (pintype "passive+no_connect"))
    )
    (net (code "117") (name "unconnected-(XP6-Pad10)") (class "Default")
      (node (ref "XP6") (pin "10") (pinfunction "10_10") (pintype "passive+no_connect"))
    )
    (net (code "118") (name "unconnected-(XP13-UTILITY-Pad2)") (class "Default")
      (node (ref "XP13") (pin "2") (pinfunction "UTILITY_2") (pintype "passive+no_connect"))
    )
  )
)
